# Sheet.net
KiCad netlist of a schematic drawn in Altium Designer
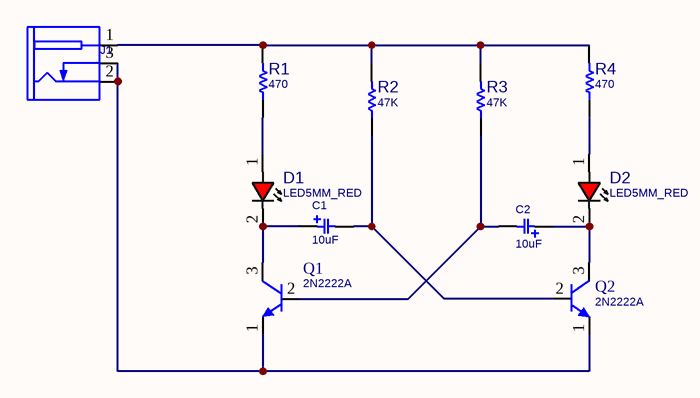
[diagram p0: Sheet.SchDoc]

(export (version "E")
  (design (tool "Eeschema 10.0.6"))
  (components
    (comp (ref "C1")
      (value "10uF")
      (footprint "C_EL_4X7")
      (description "CAP, THD, ELEC, 10uF, 25V")
      (fields (field (name "MANF") "MANF") (field (name "MANF_P#") "MANF_PART#"))
      (libsource (lib "Chila_PCB") (part "CAP_THD_EL_10u25V"))
    )
    (comp (ref "C2")
      (value "10uF")
      (footprint "C_EL_4X7")
      (description "CAP, THD, ELEC, 10uF, 25V")
      (fields (field (name "MANF") "MANF") (field (name "MANF_P#") "MANF_PART#"))
      (libsource (lib "Chila_PCB") (part "CAP_THD_EL_10u25V"))
    )
    (comp (ref "D1")
      (value "LED5MM_RED")
      (footprint "LED5MM_RED")
      (description "LED, THD, 5MM, RED")
      (fields (field (name "MANF") "MANF") (field (name "MANF_P#") "MANF_PART#"))
      (libsource (lib "Chila_PCB") (part "LED_THD_5MM_RED"))
    )
    (comp (ref "D2")
      (value "LED5MM_RED")
      (footprint "LED5MM_RED")
      (description "LED, THD, 5MM, RED")
      (fields (field (name "MANF") "MANF") (field (name "MANF_P#") "MANF_PART#"))
      (libsource (lib "Chila_PCB") (part "LED_THD_5MM_RED"))
    )
    (comp (ref "J1")
      (value "DC_POWER_JACK")
      (footprint "JAC_PWR2")
      (description "CONN, PWR JACK DC, PLUG DIAM 2.0MM RA THD")
      (fields
        (field (name "MANF") "CUI STACK")
        (field (name "MANF_P#") "PJ-202A, PJ-002AH, PJ-102AH, KLDX-0202")
      )
      (libsource (lib "Chila_PCB") (part "CONN_PWR_JACKR2"))
    )
    (comp (ref "Q1")
      (value "2N2222A")
      (footprint "TO92_3")
      (description "BJT, NPN, 40v, 0.6A, THD, TO92")
      (fields (field (name "MANF") "DIOTEC"))
      (libsource (lib "Chila_PCB") (part "NPN_2N2222A_TO92"))
    )
    (comp (ref "Q2")
      (value "2N2222A")
      (footprint "TO92_3")
      (description "BJT, NPN, 40v, 0.6A, THD, TO92")
      (fields (field (name "MANF") "DIOTEC"))
      (libsource (lib "Chila_PCB") (part "NPN_2N2222A_TO92"))
    )
    (comp (ref "R1")
      (value "470")
      (footprint "R025W_AX04")
      (description "RESISTOR, THD")
      (fields (field (name "MANF_P#") "RK73H1ETTP4701F") (field (name "MANF") "KOA SPEER"))
      (libsource (lib "Chila_PCB") (part "RES_THD"))
    )
    (comp (ref "R2")
      (value "47K")
      (footprint "R025W_AX04")
      (description "RESISTOR, THD")
      (fields (field (name "MANF_P#") "RK73H1ETTP4701F") (field (name "MANF") "KOA SPEER"))
      (libsource (lib "Chila_PCB") (part "RES_THD"))
    )
    (comp (ref "R3")
      (value "47K")
      (footprint "R025W_AX04")
      (description "RESISTOR, THD")
      (fields (field (name "MANF_P#") "RK73H1ETTP4701F") (field (name "MANF") "KOA SPEER"))
      (libsource (lib "Chila_PCB") (part "RES_THD"))
    )
    (comp (ref "R4")
      (value "470")
      (footprint "R025W_AX04")
      (description "RESISTOR, THD")
      (fields (field (name "MANF_P#") "RK73H1ETTP4701F") (field (name "MANF") "KOA SPEER"))
      (libsource (lib "Chila_PCB") (part "RES_THD"))
    )
  )
  (nets
    (net (code "1") (name "Net-(D1-ANODE)") (class "Default")
      (node (ref "D1") (pin "1") (pinfunction "ANODE_1") (pintype "passive"))
      (node (ref "R1") (pin "1") (pinfunction "1_1") (pintype "passive"))
    )
    (net (code "2") (name "Net-(D1-CATHODE)") (class "Default")
      (node (ref "C1") (pin "1") (pinfunction "1_1") (pintype "passive"))
      (node (ref "D1") (pin "2") (pinfunction "CATHODE_2") (pintype "passive"))
      (node (ref "Q1") (pin "3") (pinfunction "C_3") (pintype "passive"))
    )
    (net (code "3") (name "Net-(D2-ANODE)") (class "Default")
      (node (ref "D2") (pin "1") (pinfunction "ANODE_1") (pintype "passive"))
      (node (ref "R4") (pin "1") (pinfunction "1_1") (pintype "passive"))
    )
    (net (code "4") (name "Net-(D2-CATHODE)") (class "Default")
      (node (ref "C2") (pin "1") (pinfunction "1_1") (pintype "passive"))
      (node (ref "D2") (pin "2") (pinfunction "CATHODE_2") (pintype "passive"))
      (node (ref "Q2") (pin "3") (pinfunction "C_3") (pintype "passive"))
    )
    (net (code "5") (name "Net-(J1-INSERTION_DET)") (class "Default")
      (node (ref "J1") (pin "2") (pinfunction "SLEEVE_2") (pintype "power_in"))
      (node (ref "J1") (pin "3") (pinfunction "INSERTION_DET_3") (pintype "power_in"))
      (node (ref "Q1") (pin "1") (pinfunction "E_1") (pintype "passive"))
      (node (ref "Q2") (pin "1") (pinfunction "E_1") (pintype "passive"))
    )
    (net (code "6") (name "Net-(J1-TIP)") (class "Default")
      (node (ref "J1") (pin "1") (pinfunction "TIP_1") (pintype "power_in"))
      (node (ref "R1") (pin "2") (pinfunction "2_2") (pintype "passive"))
      (node (ref "R2") (pin "2") (pinfunction "2_2") (pintype "passive"))
      (node (ref "R3") (pin "2") (pinfunction "2_2") (pintype "passive"))
      (node (ref "R4") (pin "2") (pinfunction "2_2") (pintype "passive"))
    )
    (net (code "7") (name "Net-(Q1-B)") (class "Default")
      (node (ref "C2") (pin "2") (pinfunction "2_2") (pintype "passive"))
      (node (ref "Q1") (pin "2") (pinfunction "B_2") (pintype "passive"))
      (node (ref "R3") (pin "1") (pinfunction "1_1") (pintype "passive"))
    )
    (net (code "8") (name "Net-(Q2-B)") (class "Default")
      (node (ref "C1") (pin "2") (pinfunction "2_2") (pintype "passive"))
      (node (ref "Q2") (pin "2") (pinfunction "B_2") (pintype "passive"))
      (node (ref "R2") (pin "1") (pinfunction "1_1") (pintype "passive"))
    )
  )
)
